# tick-mk-4_6_6.net
KiCad netlist of a schematic drawn in EAGLE
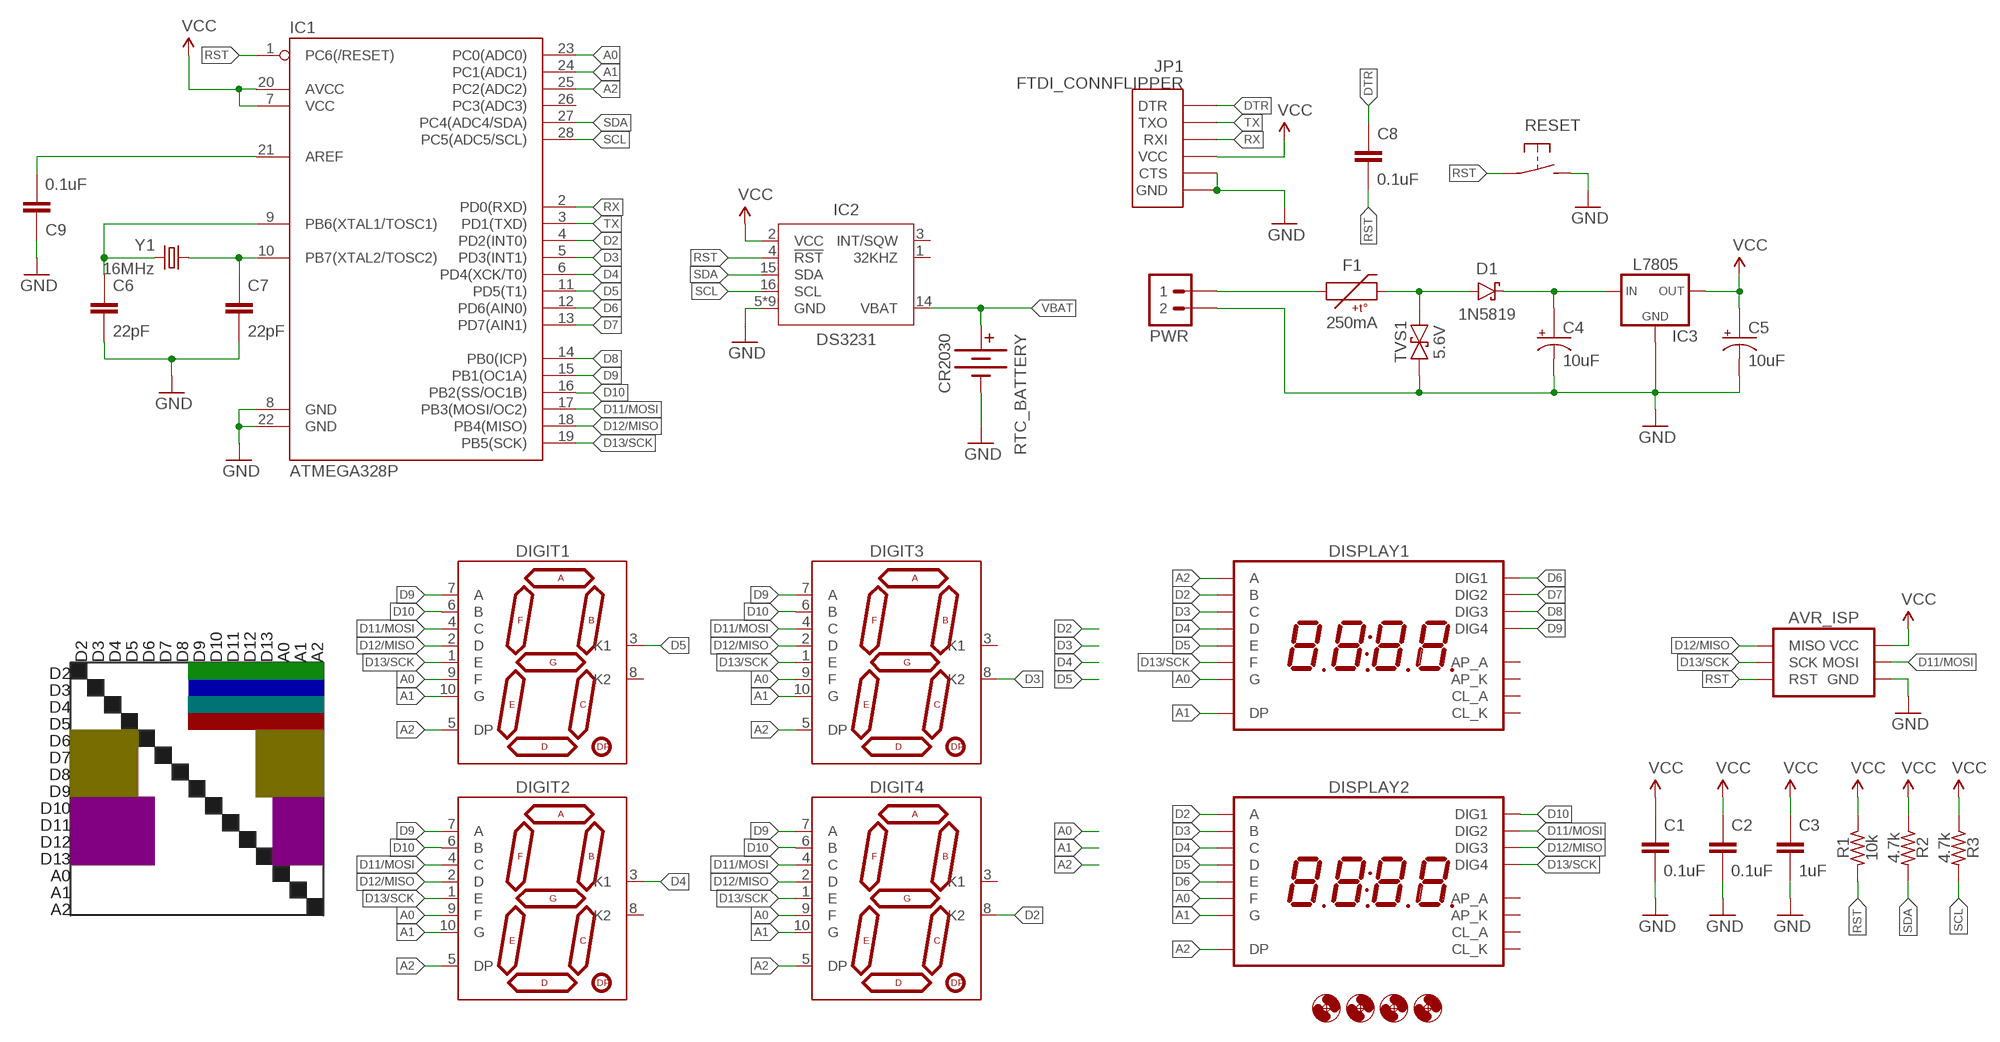
[diagram p0: schematic, sheet 1]

(export (version "E")
  (design (tool "Eeschema 10.0.6"))
  (components
    (comp (ref "AVR_ISP")
      (value "AVR_SPI_PRG_6PTH")
      (footprint "eagle-import:2X3")
      (libsource (lib "eagle-import") (part "AVR_SPI_PRG_6PTH"))
    )
    (comp (ref "C1")
      (value "0.1uF")
      (footprint "eagle-import:C025-024X044")
      (libsource (lib "eagle-import") (part "CAPACITOR-CERAMIC025-024X044"))
    )
    (comp (ref "C2")
      (value "0.1uF")
      (footprint "eagle-import:C025-024X044")
      (libsource (lib "eagle-import") (part "CAPACITOR-CERAMIC025-024X044"))
    )
    (comp (ref "C3")
      (value "1uF")
      (footprint "eagle-import:C025-024X044")
      (libsource (lib "eagle-import") (part "CAPACITOR-CERAMIC025-024X044"))
    )
    (comp (ref "C4")
      (value "10uF")
      (footprint "eagle-import:E2-5")
      (libsource (lib "eagle-import") (part "CAPACITOR-POLARIZEDE2-5"))
    )
    (comp (ref "C5")
      (value "10uF")
      (footprint "eagle-import:E2-5")
      (libsource (lib "eagle-import") (part "CAPACITOR-POLARIZEDE2-5"))
    )
    (comp (ref "C6")
      (value "22pF")
      (footprint "eagle-import:C025-024X044")
      (libsource (lib "eagle-import") (part "CAPACITOR-CERAMIC025-024X044"))
    )
    (comp (ref "C7")
      (value "22pF")
      (footprint "eagle-import:C025-024X044")
      (libsource (lib "eagle-import") (part "CAPACITOR-CERAMIC025-024X044"))
    )
    (comp (ref "C8")
      (value "0.1uF")
      (footprint "eagle-import:C025-024X044")
      (libsource (lib "eagle-import") (part "CAPACITOR-CERAMIC025-024X044"))
    )
    (comp (ref "C9")
      (value "0.1uF")
      (footprint "eagle-import:C025-024X044")
      (libsource (lib "eagle-import") (part "CAPACITOR-CERAMIC025-024X044"))
    )
    (comp (ref "D1")
      (value "1N5819")
      (footprint "eagle-import:DIODE-10.16MM")
      (libsource (lib "eagle-import") (part "DIODE-SCHOTTKYPTH-10.16MM"))
    )
    (comp (ref "DIGIT1")
      (value "7SEG_1DIGPTH-25.4MM-BARE")
      (footprint "eagle-import:7SEG_1DIG_25.4MM_NOSILK")
      (libsource (lib "eagle-import") (part "7SEG_1DIGPTH-25.4MM-BARE"))
    )
    (comp (ref "DIGIT2")
      (value "7SEG_1DIGPTH-25.4MM-BARE")
      (footprint "eagle-import:7SEG_1DIG_25.4MM_NOSILK")
      (libsource (lib "eagle-import") (part "7SEG_1DIGPTH-25.4MM-BARE"))
    )
    (comp (ref "DIGIT3")
      (value "7SEG_1DIGPTH-25.4MM-BARE")
      (footprint "eagle-import:7SEG_1DIG_25.4MM_NOSILK")
      (libsource (lib "eagle-import") (part "7SEG_1DIGPTH-25.4MM-BARE"))
    )
    (comp (ref "DIGIT4")
      (value "7SEG_1DIGPTH-25.4MM-BARE")
      (footprint "eagle-import:7SEG_1DIG_25.4MM_NOSILK")
      (libsource (lib "eagle-import") (part "7SEG_1DIGPTH-25.4MM-BARE"))
    )
    (comp (ref "DISPLAY1")
      (value "7SEG_4DIGIT_COLON_APOS")
      (footprint "eagle-import:7SEG_4DIG_10MM")
      (libsource (lib "eagle-import") (part "7SEG_4DIGIT_COLON_APOS"))
    )
    (comp (ref "DISPLAY2")
      (value "7SEG_4DIGIT_COLON_APOS")
      (footprint "eagle-import:7SEG_4DIG_10MM")
      (libsource (lib "eagle-import") (part "7SEG_4DIGIT_COLON_APOS"))
    )
    (comp (ref "F1")
      (value "250mA")
      (footprint "eagle-import:PTC-PTH-5.08MM")
      (libsource (lib "eagle-import") (part "PTCPTH-5.08MM"))
    )
    (comp (ref "H1")
      (value "HOLE#2")
      (footprint "eagle-import:HOLE-#2")
      (libsource (lib "eagle-import") (part "HOLE#2"))
    )
    (comp (ref "H2")
      (value "HOLE#2")
      (footprint "eagle-import:HOLE-#2")
      (libsource (lib "eagle-import") (part "HOLE#2"))
    )
    (comp (ref "H3")
      (value "HOLE#2")
      (footprint "eagle-import:HOLE-#2")
      (libsource (lib "eagle-import") (part "HOLE#2"))
    )
    (comp (ref "H4")
      (value "HOLE#2")
      (footprint "eagle-import:HOLE-#2")
      (libsource (lib "eagle-import") (part "HOLE#2"))
    )
    (comp (ref "IC1")
      (value "ATMEGA328P")
      (footprint "eagle-import:DIL28-3")
      (libsource (lib "eagle-import") (part "ATMEGA328P_PDIP"))
    )
    (comp (ref "IC2")
      (value "DS3231")
      (footprint "eagle-import:SO16W")
      (libsource (lib "eagle-import") (part "DS3231"))
    )
    (comp (ref "IC3")
      (value "L7805")
      (footprint "eagle-import:TO220-IGO-THERMPAD")
      (libsource (lib "eagle-import") (part "V_REG_78XXTO-220-THERMPAD"))
    )
    (comp (ref "JP1")
      (value "FTDI_CONNFLIPPER")
      (footprint "eagle-import:FTDI_CONN_FLIP")
      (libsource (lib "eagle-import") (part "FTDI_CONNFLIPPER"))
    )
    (comp (ref "PWR")
      (value "M02JST-PTH-VERT")
      (footprint "eagle-import:JST-2-PH-VERT-PTH")
      (libsource (lib "eagle-import") (part "M02JST-PTH-VERT"))
    )
    (comp (ref "R1")
      (value "10k")
      (footprint "eagle-import:RESISTOR-AXIAL-PTH-7.62MM")
      (libsource (lib "eagle-import") (part "RESISTORPTH-AXIAL-7.62MM"))
    )
    (comp (ref "R2")
      (value "4.7k")
      (footprint "eagle-import:RESISTOR-AXIAL-PTH-6.35MM")
      (libsource (lib "eagle-import") (part "RESISTORPTH-AXIAL-6.35MM"))
    )
    (comp (ref "R3")
      (value "4.7k")
      (footprint "eagle-import:RESISTOR-AXIAL-PTH-6.35MM")
      (libsource (lib "eagle-import") (part "RESISTORPTH-AXIAL-6.35MM"))
    )
    (comp (ref "RESET")
      (value "SPST-NO-TACT6MM-PTH-SMALL-PADS")
      (footprint "eagle-import:DTS-6-SMALL-PADS")
      (libsource (lib "eagle-import") (part "SPST-NO-TACT6MM-PTH-SMALL-PADS"))
    )
    (comp (ref "RTC_BATTERY")
      (value "CR2030")
      (footprint "eagle-import:BATTCON_20MM_MINE")
      (libsource (lib "eagle-import") (part "BATTERY20MMSMD-MINE"))
    )
    (comp (ref "TVS1")
      (value "5.6V")
      (footprint "eagle-import:DO-41-TVS-BI-10.16MM")
      (libsource (lib "eagle-import") (part "TVSDO-41-10.16MM"))
    )
    (comp (ref "Y1")
      (value "16MHz")
      (footprint "eagle-import:HC49U-V")
      (libsource (lib "eagle-import") (part "CRYSTALHC49UV"))
    )
  )
  (nets
    (net (code "1") (name "A0") (class "Default")
      (node (ref "DIGIT1") (pin "9") (pinfunction "F_9") (pintype "bidirectional"))
      (node (ref "DIGIT2") (pin "9") (pinfunction "F_9") (pintype "bidirectional"))
      (node (ref "DIGIT3") (pin "9") (pinfunction "F_9") (pintype "bidirectional"))
      (node (ref "DIGIT4") (pin "9") (pinfunction "F_9") (pintype "bidirectional"))
      (node (ref "DISPLAY1") (pin "15") (pinfunction "G_15") (pintype "passive"))
      (node (ref "DISPLAY2") (pin "11") (pinfunction "F_11") (pintype "passive"))
      (node (ref "IC1") (pin "23") (pinfunction "PC0(ADC0)_23") (pintype "bidirectional"))
    )
    (net (code "2") (name "A1") (class "Default")
      (node (ref "DIGIT1") (pin "10") (pinfunction "G_10") (pintype "bidirectional"))
      (node (ref "DIGIT2") (pin "10") (pinfunction "G_10") (pintype "bidirectional"))
      (node (ref "DIGIT3") (pin "10") (pinfunction "G_10") (pintype "bidirectional"))
      (node (ref "DIGIT4") (pin "10") (pinfunction "G_10") (pintype "bidirectional"))
      (node (ref "DISPLAY1") (pin "7") (pinfunction "DP_7") (pintype "passive"))
      (node (ref "DISPLAY2") (pin "15") (pinfunction "G_15") (pintype "passive"))
      (node (ref "IC1") (pin "24") (pinfunction "PC1(ADC1)_24") (pintype "bidirectional"))
    )
    (net (code "3") (name "A2") (class "Default")
      (node (ref "DIGIT1") (pin "5") (pinfunction "DP_5") (pintype "bidirectional"))
      (node (ref "DIGIT2") (pin "5") (pinfunction "DP_5") (pintype "bidirectional"))
      (node (ref "DIGIT3") (pin "5") (pinfunction "DP_5") (pintype "bidirectional"))
      (node (ref "DIGIT4") (pin "5") (pinfunction "DP_5") (pintype "bidirectional"))
      (node (ref "DISPLAY1") (pin "14") (pinfunction "A_14") (pintype "passive"))
      (node (ref "DISPLAY2") (pin "7") (pinfunction "DP_7") (pintype "passive"))
      (node (ref "IC1") (pin "25") (pinfunction "PC2(ADC2)_25") (pintype "bidirectional"))
    )
    (net (code "4") (name "D2") (class "Default")
      (node (ref "DIGIT4") (pin "8") (pinfunction "K2_8") (pintype "bidirectional"))
      (node (ref "DISPLAY1") (pin "16") (pinfunction "B_16") (pintype "passive"))
      (node (ref "DISPLAY2") (pin "14") (pinfunction "A_14") (pintype "passive"))
      (node (ref "IC1") (pin "4") (pinfunction "PD2(INT0)_4") (pintype "bidirectional"))
    )
    (net (code "5") (name "D3") (class "Default")
      (node (ref "DIGIT3") (pin "8") (pinfunction "K2_8") (pintype "bidirectional"))
      (node (ref "DISPLAY1") (pin "13") (pinfunction "C_13") (pintype "passive"))
      (node (ref "DISPLAY2") (pin "16") (pinfunction "B_16") (pintype "passive"))
      (node (ref "IC1") (pin "5") (pinfunction "PD3(INT1)_5") (pintype "bidirectional"))
    )
    (net (code "6") (name "D4") (class "Default")
      (node (ref "DIGIT2") (pin "3") (pinfunction "K1_3") (pintype "bidirectional"))
      (node (ref "DISPLAY1") (pin "3") (pinfunction "D_3") (pintype "passive"))
      (node (ref "DISPLAY2") (pin "13") (pinfunction "C_13") (pintype "passive"))
      (node (ref "IC1") (pin "6") (pinfunction "PD4(XCK/T0)_6") (pintype "bidirectional"))
    )
    (net (code "7") (name "D5") (class "Default")
      (node (ref "DIGIT1") (pin "3") (pinfunction "K1_3") (pintype "bidirectional"))
      (node (ref "DISPLAY1") (pin "5") (pinfunction "E_5") (pintype "passive"))
      (node (ref "DISPLAY2") (pin "3") (pinfunction "D_3") (pintype "passive"))
      (node (ref "IC1") (pin "11") (pinfunction "PD5(T1)_11") (pintype "bidirectional"))
    )
    (net (code "8") (name "D6") (class "Default")
      (node (ref "DISPLAY1") (pin "1") (pinfunction "DIG1_1") (pintype "passive"))
      (node (ref "DISPLAY2") (pin "5") (pinfunction "E_5") (pintype "passive"))
      (node (ref "IC1") (pin "12") (pinfunction "PD6(AIN0)_12") (pintype "bidirectional"))
    )
    (net (code "9") (name "D7") (class "Default")
      (node (ref "DISPLAY1") (pin "2") (pinfunction "DIG2_2") (pintype "passive"))
      (node (ref "IC1") (pin "13") (pinfunction "PD7(AIN1)_13") (pintype "bidirectional"))
    )
    (net (code "10") (name "D8") (class "Default")
      (node (ref "DISPLAY1") (pin "6") (pinfunction "DIG3_6") (pintype "passive"))
      (node (ref "IC1") (pin "14") (pinfunction "PB0(ICP)_14") (pintype "bidirectional"))
    )
    (net (code "11") (name "D9") (class "Default")
      (node (ref "DIGIT1") (pin "7") (pinfunction "A_7") (pintype "bidirectional"))
      (node (ref "DIGIT2") (pin "7") (pinfunction "A_7") (pintype "bidirectional"))
      (node (ref "DIGIT3") (pin "7") (pinfunction "A_7") (pintype "bidirectional"))
      (node (ref "DIGIT4") (pin "7") (pinfunction "A_7") (pintype "bidirectional"))
      (node (ref "DISPLAY1") (pin "8") (pinfunction "DIG4_8") (pintype "passive"))
      (node (ref "IC1") (pin "15") (pinfunction "PB1(OC1A)_15") (pintype "bidirectional"))
    )
    (net (code "12") (name "D10") (class "Default")
      (node (ref "DIGIT1") (pin "6") (pinfunction "B_6") (pintype "bidirectional"))
      (node (ref "DIGIT2") (pin "6") (pinfunction "B_6") (pintype "bidirectional"))
      (node (ref "DIGIT3") (pin "6") (pinfunction "B_6") (pintype "bidirectional"))
      (node (ref "DIGIT4") (pin "6") (pinfunction "B_6") (pintype "bidirectional"))
      (node (ref "DISPLAY2") (pin "1") (pinfunction "DIG1_1") (pintype "passive"))
      (node (ref "IC1") (pin "16") (pinfunction "PB2(SS/OC1B)_16") (pintype "bidirectional"))
    )
    (net (code "13") (name "D11{slash}MOSI") (class "Default")
      (node (ref "AVR_ISP") (pin "4") (pinfunction "MOSI_4") (pintype "passive"))
      (node (ref "DIGIT1") (pin "4") (pinfunction "C_4") (pintype "bidirectional"))
      (node (ref "DIGIT2") (pin "4") (pinfunction "C_4") (pintype "bidirectional"))
      (node (ref "DIGIT3") (pin "4") (pinfunction "C_4") (pintype "bidirectional"))
      (node (ref "DIGIT4") (pin "4") (pinfunction "C_4") (pintype "bidirectional"))
      (node (ref "DISPLAY2") (pin "2") (pinfunction "DIG2_2") (pintype "passive"))
      (node (ref "IC1") (pin "17") (pinfunction "PB3(MOSI/OC2)_17") (pintype "bidirectional"))
    )
    (net (code "14") (name "D12{slash}MISO") (class "Default")
      (node (ref "AVR_ISP") (pin "1") (pinfunction "MISO_1") (pintype "passive"))
      (node (ref "DIGIT1") (pin "2") (pinfunction "D_2") (pintype "bidirectional"))
      (node (ref "DIGIT2") (pin "2") (pinfunction "D_2") (pintype "bidirectional"))
      (node (ref "DIGIT3") (pin "2") (pinfunction "D_2") (pintype "bidirectional"))
      (node (ref "DIGIT4") (pin "2") (pinfunction "D_2") (pintype "bidirectional"))
      (node (ref "DISPLAY2") (pin "6") (pinfunction "DIG3_6") (pintype "passive"))
      (node (ref "IC1") (pin "18") (pinfunction "PB4(MISO)_18") (pintype "bidirectional"))
    )
    (net (code "15") (name "D13{slash}SCK") (class "Default")
      (node (ref "AVR_ISP") (pin "3") (pinfunction "SCK_3") (pintype "passive"))
      (node (ref "DIGIT1") (pin "1") (pinfunction "E_1") (pintype "bidirectional"))
      (node (ref "DIGIT2") (pin "1") (pinfunction "E_1") (pintype "bidirectional"))
      (node (ref "DIGIT3") (pin "1") (pinfunction "E_1") (pintype "bidirectional"))
      (node (ref "DIGIT4") (pin "1") (pinfunction "E_1") (pintype "bidirectional"))
      (node (ref "DISPLAY1") (pin "11") (pinfunction "F_11") (pintype "passive"))
      (node (ref "DISPLAY2") (pin "8") (pinfunction "DIG4_8") (pintype "passive"))
      (node (ref "IC1") (pin "19") (pinfunction "PB5(SCK)_19") (pintype "bidirectional"))
    )
    (net (code "16") (name "DTR") (class "Default")
      (node (ref "C8") (pin "1") (pinfunction "1_1") (pintype "passive"))
      (node (ref "JP1") (pin "DTR") (pinfunction "DTR_DTR") (pintype "bidirectional"))
    )
    (net (code "17") (name "GND") (class "Default")
      (node (ref "AVR_ISP") (pin "6") (pinfunction "GND_6") (pintype "passive"))
      (node (ref "C1") (pin "2") (pinfunction "2_2") (pintype "passive"))
      (node (ref "C2") (pin "2") (pinfunction "2_2") (pintype "passive"))
      (node (ref "C3") (pin "2") (pinfunction "2_2") (pintype "passive"))
      (node (ref "C4") (pin "-") (pinfunction "-_-") (pintype "passive"))
      (node (ref "C5") (pin "-") (pinfunction "-_-") (pintype "passive"))
      (node (ref "C6") (pin "2") (pinfunction "2_2") (pintype "passive"))
      (node (ref "C7") (pin "2") (pinfunction "2_2") (pintype "passive"))
      (node (ref "C9") (pin "1") (pinfunction "1_1") (pintype "passive"))
      (node (ref "IC1") (pin "22") (pinfunction "GND_22") (pintype "bidirectional"))
      (node (ref "IC1") (pin "8") (pinfunction "GND_8") (pintype "bidirectional"))
      (node (ref "IC2") (pin "10") (pinfunction "GND_10") (pintype "bidirectional"))
      (node (ref "IC2") (pin "11") (pinfunction "GND_11") (pintype "bidirectional"))
      (node (ref "IC2") (pin "12") (pinfunction "GND_12") (pintype "bidirectional"))
      (node (ref "IC2") (pin "13") (pinfunction "GND_13") (pintype "bidirectional"))
      (node (ref "IC2") (pin "5") (pinfunction "GND_5") (pintype "bidirectional"))
      (node (ref "IC2") (pin "6") (pinfunction "GND_6") (pintype "bidirectional"))
      (node (ref "IC2") (pin "7") (pinfunction "GND_7") (pintype "bidirectional"))
      (node (ref "IC2") (pin "8") (pinfunction "GND_8") (pintype "bidirectional"))
      (node (ref "IC2") (pin "9") (pinfunction "GND_9") (pintype "bidirectional"))
      (node (ref "IC3") (pin "4") (pinfunction "GND_4") (pintype "bidirectional"))
      (node (ref "IC3") (pin "GND") (pinfunction "GND_GND") (pintype "bidirectional"))
      (node (ref "JP1") (pin "CTS") (pinfunction "CTS_CTS") (pintype "bidirectional"))
      (node (ref "JP1") (pin "GND") (pinfunction "GND_GND") (pintype "bidirectional"))
      (node (ref "PWR") (pin "2") (pinfunction "2_2") (pintype "passive"))
      (node (ref "RESET") (pin "3") (pinfunction "2_3") (pintype "passive"))
      (node (ref "RESET") (pin "4") (pinfunction "2_4") (pintype "passive"))
      (node (ref "RTC_BATTERY") (pin "BOTTOM") (pinfunction "-_BOTTOM") (pintype "power_in"))
      (node (ref "TVS1") (pin "P$1") (pinfunction "1_P$1") (pintype "passive"))
    )
    (net (code "18") (name "Net-(C4-Pad+)") (class "Default")
      (node (ref "C4") (pin "+") (pinfunction "+_+") (pintype "passive"))
      (node (ref "D1") (pin "C") (pinfunction "C_C") (pintype "passive"))
      (node (ref "IC3") (pin "IN") (pinfunction "IN_IN") (pintype "bidirectional"))
    )
    (net (code "19") (name "Net-(F1-1)") (class "Default")
      (node (ref "F1") (pin "P$1") (pinfunction "1_P$1") (pintype "passive"))
      (node (ref "PWR") (pin "1") (pinfunction "1_1") (pintype "passive"))
    )
    (net (code "20") (name "Net-(F1-2)") (class "Default")
      (node (ref "D1") (pin "A") (pinfunction "A_A") (pintype "passive"))
      (node (ref "F1") (pin "P$2") (pinfunction "2_P$2") (pintype "passive"))
      (node (ref "TVS1") (pin "P$2") (pinfunction "2_P$2") (pintype "passive"))
    )
    (net (code "21") (name "Net-(IC1-AREF)") (class "Default")
      (node (ref "C9") (pin "2") (pinfunction "2_2") (pintype "passive"))
      (node (ref "IC1") (pin "21") (pinfunction "AREF_21") (pintype "bidirectional"))
    )
    (net (code "22") (name "Net-(IC1-PB6(XTAL1{slash}TOSC1))") (class "Default")
      (node (ref "C6") (pin "1") (pinfunction "1_1") (pintype "passive"))
      (node (ref "IC1") (pin "9") (pinfunction "PB6(XTAL1/TOSC1)_9") (pintype "bidirectional"))
      (node (ref "Y1") (pin "2") (pinfunction "2_2") (pintype "passive"))
    )
    (net (code "23") (name "Net-(IC1-PB7(XTAL2{slash}TOSC2))") (class "Default")
      (node (ref "C7") (pin "1") (pinfunction "1_1") (pintype "passive"))
      (node (ref "IC1") (pin "10") (pinfunction "PB7(XTAL2/TOSC2)_10") (pintype "bidirectional"))
      (node (ref "Y1") (pin "1") (pinfunction "1_1") (pintype "passive"))
    )
    (net (code "24") (name "RST") (class "Default")
      (node (ref "AVR_ISP") (pin "5") (pinfunction "RST_5") (pintype "passive"))
      (node (ref "C8") (pin "2") (pinfunction "2_2") (pintype "passive"))
      (node (ref "IC1") (pin "1") (pinfunction "PC6(/RESET)_1") (pintype "bidirectional"))
      (node (ref "IC2") (pin "4") (pinfunction "~{RST}_4") (pintype "bidirectional"))
      (node (ref "R1") (pin "P$2") (pinfunction "2_P$2") (pintype "passive"))
      (node (ref "RESET") (pin "1") (pinfunction "1_1") (pintype "passive"))
      (node (ref "RESET") (pin "2") (pinfunction "1_2") (pintype "passive"))
    )
    (net (code "25") (name "RX") (class "Default")
      (node (ref "IC1") (pin "2") (pinfunction "PD0(RXD)_2") (pintype "bidirectional"))
      (node (ref "JP1") (pin "RXI") (pinfunction "RXI_RXI") (pintype "bidirectional"))
    )
    (net (code "26") (name "SCL") (class "Default")
      (node (ref "IC1") (pin "28") (pinfunction "PC5(ADC5/SCL)_28") (pintype "bidirectional"))
      (node (ref "IC2") (pin "16") (pinfunction "SCL_16") (pintype "bidirectional"))
      (node (ref "R3") (pin "P$2") (pinfunction "2_P$2") (pintype "passive"))
    )
    (net (code "27") (name "SDA") (class "Default")
      (node (ref "IC1") (pin "27") (pinfunction "PC4(ADC4/SDA)_27") (pintype "bidirectional"))
      (node (ref "IC2") (pin "15") (pinfunction "SDA_15") (pintype "bidirectional"))
      (node (ref "R2") (pin "P$2") (pinfunction "2_P$2") (pintype "passive"))
    )
    (net (code "28") (name "TX") (class "Default")
      (node (ref "IC1") (pin "3") (pinfunction "PD1(TXD)_3") (pintype "bidirectional"))
      (node (ref "JP1") (pin "TXO") (pinfunction "TXO_TXO") (pintype "bidirectional"))
    )
    (net (code "29") (name "VBAT") (class "Default")
      (node (ref "IC2") (pin "14") (pinfunction "VBAT_14") (pintype "bidirectional"))
      (node (ref "RTC_BATTERY") (pin "TOP@1") (pinfunction "+_TOP@1") (pintype "power_in"))
      (node (ref "RTC_BATTERY") (pin "TOP@2") (pinfunction "+_TOP@2") (pintype "power_in"))
    )
    (net (code "30") (name "VCC") (class "Default")
      (node (ref "AVR_ISP") (pin "2") (pinfunction "VCC_2") (pintype "passive"))
      (node (ref "C1") (pin "1") (pinfunction "1_1") (pintype "passive"))
      (node (ref "C2") (pin "1") (pinfunction "1_1") (pintype "passive"))
      (node (ref "C3") (pin "1") (pinfunction "1_1") (pintype "passive"))
      (node (ref "C5") (pin "+") (pinfunction "+_+") (pintype "passive"))
      (node (ref "IC1") (pin "20") (pinfunction "AVCC_20") (pintype "bidirectional"))
      (node (ref "IC1") (pin "7") (pinfunction "VCC_7") (pintype "bidirectional"))
      (node (ref "IC2") (pin "2") (pinfunction "VCC_2") (pintype "bidirectional"))
      (node (ref "IC3") (pin "OUT") (pinfunction "OUT_OUT") (pintype "bidirectional"))
      (node (ref "JP1") (pin "VCC") (pinfunction "VCC_VCC") (pintype "bidirectional"))
      (node (ref "R1") (pin "P$1") (pinfunction "1_P$1") (pintype "passive"))
      (node (ref "R2") (pin "P$1") (pinfunction "1_P$1") (pintype "passive"))
      (node (ref "R3") (pin "P$1") (pinfunction "1_P$1") (pintype "passive"))
    )
    (net (code "31") (name "unconnected-(DIGIT1-K2-Pad8)") (class "Default")
      (node (ref "DIGIT1") (pin "8") (pinfunction "K2_8") (pintype "bidirectional"))
    )
    (net (code "32") (name "unconnected-(DIGIT2-K2-Pad8)") (class "Default")
      (node (ref "DIGIT2") (pin "8") (pinfunction "K2_8") (pintype "bidirectional"))
    )
    (net (code "33") (name "unconnected-(DIGIT3-K1-Pad3)") (class "Default")
      (node (ref "DIGIT3") (pin "3") (pinfunction "K1_3") (pintype "bidirectional"))
    )
    (net (code "34") (name "unconnected-(DIGIT4-K1-Pad3)") (class "Default")
      (node (ref "DIGIT4") (pin "3") (pinfunction "K1_3") (pintype "bidirectional"))
    )
    (net (code "35") (name "unconnected-(DISPLAY1-AP_A-Pad10)") (class "Default")
      (node (ref "DISPLAY1") (pin "10") (pinfunction "AP_A_10") (pintype "bidirectional"))
    )
    (net (code "36") (name "unconnected-(DISPLAY1-AP_K-Pad9)") (class "Default")
      (node (ref "DISPLAY1") (pin "9") (pinfunction "AP_K_9") (pintype "bidirectional"))
    )
    (net (code "37") (name "unconnected-(DISPLAY1-CL_A-Pad4)") (class "Default")
      (node (ref "DISPLAY1") (pin "4") (pinfunction "CL_A_4") (pintype "passive"))
    )
    (net (code "38") (name "unconnected-(DISPLAY1-CL_K-Pad12)") (class "Default")
      (node (ref "DISPLAY1") (pin "12") (pinfunction "CL_K_12") (pintype "passive"))
    )
    (net (code "39") (name "unconnected-(DISPLAY2-AP_A-Pad10)") (class "Default")
      (node (ref "DISPLAY2") (pin "10") (pinfunction "AP_A_10") (pintype "bidirectional"))
    )
    (net (code "40") (name "unconnected-(DISPLAY2-AP_K-Pad9)") (class "Default")
      (node (ref "DISPLAY2") (pin "9") (pinfunction "AP_K_9") (pintype "bidirectional"))
    )
    (net (code "41") (name "unconnected-(DISPLAY2-CL_A-Pad4)") (class "Default")
      (node (ref "DISPLAY2") (pin "4") (pinfunction "CL_A_4") (pintype "passive"))
    )
    (net (code "42") (name "unconnected-(DISPLAY2-CL_K-Pad12)") (class "Default")
      (node (ref "DISPLAY2") (pin "12") (pinfunction "CL_K_12") (pintype "passive"))
    )
    (net (code "43") (name "unconnected-(IC1-PC3(ADC3)-Pad26)") (class "Default")
      (node (ref "IC1") (pin "26") (pinfunction "PC3(ADC3)_26") (pintype "bidirectional"))
    )
    (net (code "44") (name "unconnected-(IC2-32KHZ-Pad1)") (class "Default")
      (node (ref "IC2") (pin "1") (pinfunction "32KHZ_1") (pintype "bidirectional"))
    )
    (net (code "45") (name "unconnected-(IC2-INT{slash}SQW-Pad3)") (class "Default")
      (node (ref "IC2") (pin "3") (pinfunction "INT/SQW_3") (pintype "bidirectional"))
    )
  )
)
